# MIDIThereminCPU.net
KiCad netlist of a schematic drawn in EAGLE
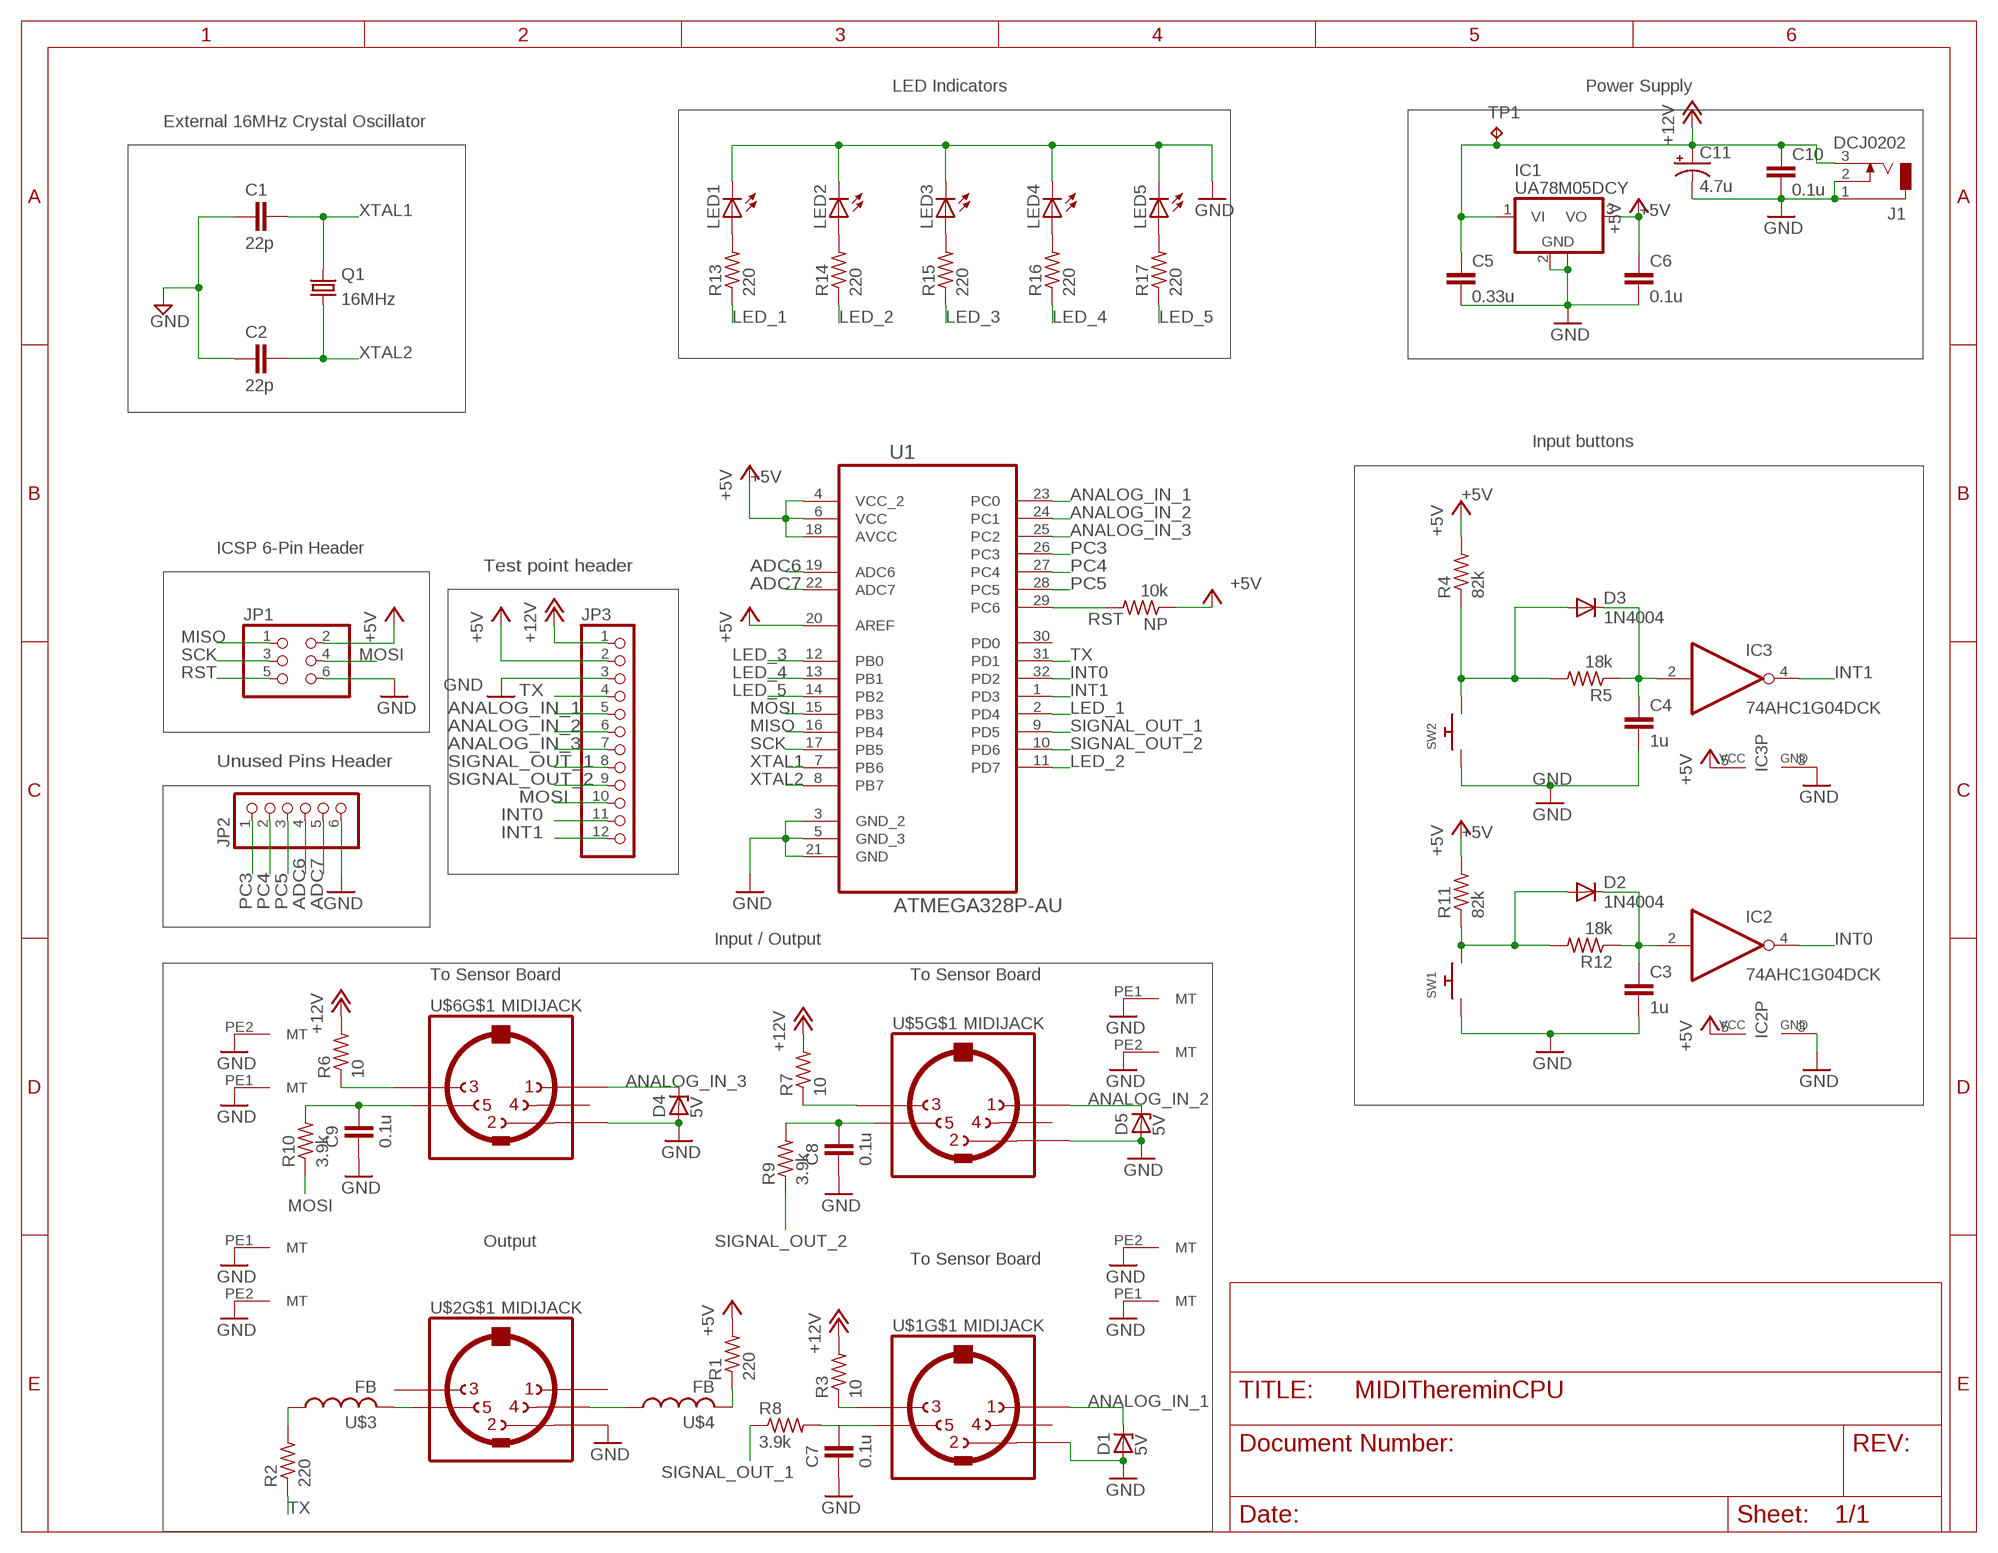
[diagram p0: schematic, sheet 1]

(export (version "E")
  (design (tool "Eeschema 10.0.6"))
  (components
    (comp (ref "C1")
      (value "22p")
      (footprint "eagle-import:C2.5-3")
      (libsource (lib "eagle-import") (part "C2,5-3"))
    )
    (comp (ref "C2")
      (value "22p")
      (footprint "eagle-import:C2.5-3")
      (libsource (lib "eagle-import") (part "C2,5-3"))
    )
    (comp (ref "C3")
      (value "1u")
      (footprint "eagle-import:C2.5-3")
      (libsource (lib "eagle-import") (part "C2,5-3"))
    )
    (comp (ref "C4")
      (value "1u")
      (footprint "eagle-import:C2.5-3")
      (libsource (lib "eagle-import") (part "C2,5-3"))
    )
    (comp (ref "C5")
      (value "0.33u")
      (footprint "eagle-import:C2.5-3")
      (libsource (lib "eagle-import") (part "C2,5-3"))
    )
    (comp (ref "C6")
      (value "0.1u")
      (footprint "eagle-import:C2.5-3")
      (libsource (lib "eagle-import") (part "C2,5-3"))
    )
    (comp (ref "C7")
      (value "0.1u")
      (footprint "eagle-import:C2.5-3")
      (libsource (lib "eagle-import") (part "C2,5-3"))
    )
    (comp (ref "C8")
      (value "0.1u")
      (footprint "eagle-import:C2.5-3")
      (libsource (lib "eagle-import") (part "C2,5-3"))
    )
    (comp (ref "C9")
      (value "0.1u")
      (footprint "eagle-import:C2.5-3")
      (libsource (lib "eagle-import") (part "C2,5-3"))
    )
    (comp (ref "C10")
      (value "0.1u")
      (footprint "eagle-import:C2.5-3")
      (libsource (lib "eagle-import") (part "C2,5-3"))
    )
    (comp (ref "C11")
      (value "4.7u")
      (footprint "eagle-import:E3,5-8")
      (libsource (lib "eagle-import") (part "CPOL-USE3.5-8"))
    )
    (comp (ref "D1")
      (value "5V")
      (footprint "eagle-import:P1Z12")
      (libsource (lib "eagle-import") (part "ZENER-DIODEP1-Z12"))
    )
    (comp (ref "D2")
      (value "1N4004")
      (footprint "eagle-import:DO41-10")
      (libsource (lib "eagle-import") (part "1N4004"))
    )
    (comp (ref "D3")
      (value "1N4004")
      (footprint "eagle-import:DO41-10")
      (libsource (lib "eagle-import") (part "1N4004"))
    )
    (comp (ref "D4")
      (value "5V")
      (footprint "eagle-import:P1Z12")
      (libsource (lib "eagle-import") (part "ZENER-DIODEP1-Z12"))
    )
    (comp (ref "D5")
      (value "5V")
      (footprint "eagle-import:P1Z12")
      (libsource (lib "eagle-import") (part "ZENER-DIODEP1-Z12"))
    )
    (comp (ref "IC1")
      (value "UA78M05DCY")
      (footprint "eagle-import:SOT223")
      (libsource (lib "eagle-import") (part "UA78MDCY05"))
    )
    (comp (ref "IC2")
      (value "74AHC1G04DCK")
      (footprint "eagle-import:SC70-5")
      (libsource (lib "eagle-import") (part "741G04DCKAHC"))
    )
    (comp (ref "IC3")
      (value "74AHC1G04DCK")
      (footprint "eagle-import:SC70-5")
      (libsource (lib "eagle-import") (part "741G04DCKAHC"))
    )
    (comp (ref "J1")
      (value "DCJ0202")
      (footprint "eagle-import:DCJ0202")
      (libsource (lib "eagle-import") (part "DCJ0202"))
    )
    (comp (ref "JP1")
      (value "PINHD-2X3")
      (footprint "eagle-import:2X03")
      (libsource (lib "eagle-import") (part "PINHD-2X3"))
    )
    (comp (ref "JP2")
      (value "PINHD-1X6")
      (footprint "eagle-import:1X06")
      (libsource (lib "eagle-import") (part "PINHD-1X6"))
    )
    (comp (ref "JP3")
      (value "PINHD-1X12")
      (footprint "eagle-import:1X12")
      (libsource (lib "eagle-import") (part "PINHD-1X12"))
    )
    (comp (ref "LED1")
      (value "LEDB155")
      (footprint "eagle-import:Q62902-B155")
      (libsource (lib "eagle-import") (part "LEDB155"))
    )
    (comp (ref "LED2")
      (value "LEDB155")
      (footprint "eagle-import:Q62902-B155")
      (libsource (lib "eagle-import") (part "LEDB155"))
    )
    (comp (ref "LED3")
      (value "LEDB155")
      (footprint "eagle-import:Q62902-B155")
      (libsource (lib "eagle-import") (part "LEDB155"))
    )
    (comp (ref "LED4")
      (value "LEDB155")
      (footprint "eagle-import:Q62902-B155")
      (libsource (lib "eagle-import") (part "LEDB155"))
    )
    (comp (ref "LED5")
      (value "LEDB155")
      (footprint "eagle-import:Q62902-B155")
      (libsource (lib "eagle-import") (part "LEDB155"))
    )
    (comp (ref "NP")
      (value "10k")
      (footprint "eagle-import:0207_10")
      (libsource (lib "eagle-import") (part "R-US_0207/10"))
    )
    (comp (ref "Q1")
      (value "16MHz")
      (footprint "eagle-import:SM49")
      (libsource (lib "eagle-import") (part "CRYSTALSM49"))
    )
    (comp (ref "R1")
      (value "220")
      (footprint "eagle-import:0207_10")
      (libsource (lib "eagle-import") (part "R-US_0207/10"))
    )
    (comp (ref "R2")
      (value "220")
      (footprint "eagle-import:0207_10")
      (libsource (lib "eagle-import") (part "R-US_0207/10"))
    )
    (comp (ref "R3")
      (value "10")
      (footprint "eagle-import:0207_10")
      (libsource (lib "eagle-import") (part "R-US_0207/10"))
    )
    (comp (ref "R4")
      (value "82k")
      (footprint "eagle-import:0207_10")
      (libsource (lib "eagle-import") (part "R-US_0207/10"))
    )
    (comp (ref "R5")
      (value "18k")
      (footprint "eagle-import:0207_10")
      (libsource (lib "eagle-import") (part "R-US_0207/10"))
    )
    (comp (ref "R6")
      (value "10")
      (footprint "eagle-import:0207_10")
      (libsource (lib "eagle-import") (part "R-US_0207/10"))
    )
    (comp (ref "R7")
      (value "10")
      (footprint "eagle-import:0207_10")
      (libsource (lib "eagle-import") (part "R-US_0207/10"))
    )
    (comp (ref "R8")
      (value "3.9k")
      (footprint "eagle-import:0207_10")
      (libsource (lib "eagle-import") (part "R-US_0207/10"))
    )
    (comp (ref "R9")
      (value "3.9k")
      (footprint "eagle-import:0207_10")
      (libsource (lib "eagle-import") (part "R-US_0207/10"))
    )
    (comp (ref "R10")
      (value "3.9k")
      (footprint "eagle-import:0207_10")
      (libsource (lib "eagle-import") (part "R-US_0207/10"))
    )
    (comp (ref "R11")
      (value "82k")
      (footprint "eagle-import:0207_10")
      (libsource (lib "eagle-import") (part "R-US_0207/10"))
    )
    (comp (ref "R12")
      (value "18k")
      (footprint "eagle-import:0207_10")
      (libsource (lib "eagle-import") (part "R-US_0207/10"))
    )
    (comp (ref "R13")
      (value "220")
      (footprint "eagle-import:0207_10")
      (libsource (lib "eagle-import") (part "R-US_0207/10"))
    )
    (comp (ref "R14")
      (value "220")
      (footprint "eagle-import:0207_10")
      (libsource (lib "eagle-import") (part "R-US_0207/10"))
    )
    (comp (ref "R15")
      (value "220")
      (footprint "eagle-import:0207_10")
      (libsource (lib "eagle-import") (part "R-US_0207/10"))
    )
    (comp (ref "R16")
      (value "220")
      (footprint "eagle-import:0207_10")
      (libsource (lib "eagle-import") (part "R-US_0207/10"))
    )
    (comp (ref "R17")
      (value "220")
      (footprint "eagle-import:0207_10")
      (libsource (lib "eagle-import") (part "R-US_0207/10"))
    )
    (comp (ref "SW1")
      (value "SWITCH_PUSHBUTTONSOFTTOUCHSMD_SJ")
      (footprint "eagle-import:PUSHBUTTON_SMD_SJ")
      (libsource (lib "eagle-import") (part "SWITCH_PUSHBUTTONSOFTTOUCHSMD_SJ"))
    )
    (comp (ref "SW2")
      (value "SWITCH_PUSHBUTTONSOFTTOUCHSMD_SJ")
      (footprint "eagle-import:PUSHBUTTON_SMD_SJ")
      (libsource (lib "eagle-import") (part "SWITCH_PUSHBUTTONSOFTTOUCHSMD_SJ"))
    )
    (comp (ref "TP1")
      (value "TPTP15SQ")
      (footprint "eagle-import:TP15SQ")
      (libsource (lib "eagle-import") (part "TPTP15SQ"))
    )
    (comp (ref "U$1")
      (value "MIDIJACK")
      (footprint "eagle-import:CP-2350")
      (libsource (lib "eagle-import") (part "MIDIJACK"))
    )
    (comp (ref "U$2")
      (value "MIDIJACK")
      (footprint "eagle-import:CP-2350")
      (libsource (lib "eagle-import") (part "MIDIJACK"))
    )
    (comp (ref "U$3") (value "FB") (footprint "eagle-import:FB") (libsource (lib "eagle-import") (part "FB")))
    (comp (ref "U$4") (value "FB") (footprint "eagle-import:FB") (libsource (lib "eagle-import") (part "FB")))
    (comp (ref "U$5")
      (value "MIDIJACK")
      (footprint "eagle-import:CP-2350")
      (libsource (lib "eagle-import") (part "MIDIJACK"))
    )
    (comp (ref "U$6")
      (value "MIDIJACK")
      (footprint "eagle-import:CP-2350")
      (libsource (lib "eagle-import") (part "MIDIJACK"))
    )
    (comp (ref "U1")
      (value "ATMEGA328P-AU")
      (footprint "eagle-import:QFP80P900X900X120-32N")
      (libsource (lib "eagle-import") (part "ATMEGA328P-AU"))
    )
  )
  (nets
    (net (code "1") (name "+5V") (class "Default")
      (node (ref "C6") (pin "1") (pinfunction "1_1") (pintype "passive"))
      (node (ref "IC1") (pin "3") (pinfunction "VO_3") (pintype "passive"))
      (node (ref "IC2") (pin "5") (pinfunction "VCC_5") (pintype "power_in"))
      (node (ref "IC3") (pin "5") (pinfunction "VCC_5") (pintype "power_in"))
      (node (ref "JP1") (pin "2") (pinfunction "2_2") (pintype "passive"))
      (node (ref "JP3") (pin "2") (pinfunction "2_2") (pintype "passive"))
      (node (ref "NP") (pin "1") (pinfunction "1_1") (pintype "passive"))
      (node (ref "R1") (pin "2") (pinfunction "2_2") (pintype "passive"))
      (node (ref "R11") (pin "2") (pinfunction "2_2") (pintype "passive"))
      (node (ref "R4") (pin "2") (pinfunction "2_2") (pintype "passive"))
      (node (ref "U1") (pin "18") (pinfunction "AVCC_18") (pintype "power_in"))
      (node (ref "U1") (pin "20") (pinfunction "AREF_20") (pintype "input"))
      (node (ref "U1") (pin "4") (pinfunction "VCC_2_4") (pintype "power_in"))
      (node (ref "U1") (pin "6") (pinfunction "VCC_6") (pintype "power_in"))
    )
    (net (code "2") (name "+12V") (class "Default")
      (node (ref "C10") (pin "1") (pinfunction "1_1") (pintype "passive"))
      (node (ref "C11") (pin "+") (pinfunction "+_+") (pintype "passive"))
      (node (ref "C5") (pin "1") (pinfunction "1_1") (pintype "passive"))
      (node (ref "IC1") (pin "1") (pinfunction "VI_1") (pintype "input"))
      (node (ref "J1") (pin "3") (pinfunction "3_3") (pintype "passive"))
      (node (ref "JP3") (pin "1") (pinfunction "1_1") (pintype "passive"))
      (node (ref "R3") (pin "2") (pinfunction "2_2") (pintype "passive"))
      (node (ref "R6") (pin "2") (pinfunction "2_2") (pintype "passive"))
      (node (ref "R7") (pin "2") (pinfunction "2_2") (pintype "passive"))
      (node (ref "TP1") (pin "TP") (pinfunction "TP_TP") (pintype "input"))
    )
    (net (code "3") (name "/ADC6") (class "Default")
      (node (ref "JP2") (pin "4") (pinfunction "4_4") (pintype "passive"))
      (node (ref "U1") (pin "19") (pinfunction "ADC6_19") (pintype "input"))
    )
    (net (code "4") (name "/ADC7") (class "Default")
      (node (ref "JP2") (pin "5") (pinfunction "5_5") (pintype "passive"))
      (node (ref "U1") (pin "22") (pinfunction "ADC7_22") (pintype "input"))
    )
    (net (code "5") (name "/ANALOG_IN_1") (class "Default")
      (node (ref "D1") (pin "C") (pinfunction "C_C") (pintype "passive"))
      (node (ref "JP3") (pin "5") (pinfunction "5_5") (pintype "passive"))
      (node (ref "U$1") (pin "1") (pinfunction "1_1") (pintype "passive"))
      (node (ref "U1") (pin "23") (pinfunction "PC0_23") (pintype "bidirectional"))
    )
    (net (code "6") (name "/ANALOG_IN_2") (class "Default")
      (node (ref "D5") (pin "C") (pinfunction "C_C") (pintype "passive"))
      (node (ref "JP3") (pin "6") (pinfunction "6_6") (pintype "passive"))
      (node (ref "U$5") (pin "1") (pinfunction "1_1") (pintype "passive"))
      (node (ref "U1") (pin "24") (pinfunction "PC1_24") (pintype "bidirectional"))
    )
    (net (code "7") (name "/ANALOG_IN_3") (class "Default")
      (node (ref "D4") (pin "C") (pinfunction "C_C") (pintype "passive"))
      (node (ref "JP3") (pin "7") (pinfunction "7_7") (pintype "passive"))
      (node (ref "U$6") (pin "1") (pinfunction "1_1") (pintype "passive"))
      (node (ref "U1") (pin "25") (pinfunction "PC2_25") (pintype "bidirectional"))
    )
    (net (code "8") (name "/INT0") (class "Default")
      (node (ref "IC2") (pin "4") (pinfunction "O_4") (pintype "output"))
      (node (ref "JP3") (pin "11") (pinfunction "11_11") (pintype "passive"))
      (node (ref "U1") (pin "32") (pinfunction "PD2_32") (pintype "bidirectional"))
    )
    (net (code "9") (name "/INT1") (class "Default")
      (node (ref "IC3") (pin "4") (pinfunction "O_4") (pintype "output"))
      (node (ref "JP3") (pin "12") (pinfunction "12_12") (pintype "passive"))
      (node (ref "U1") (pin "1") (pinfunction "PD3_1") (pintype "bidirectional"))
    )
    (net (code "10") (name "/LED_1") (class "Default")
      (node (ref "R13") (pin "1") (pinfunction "1_1") (pintype "passive"))
      (node (ref "U1") (pin "2") (pinfunction "PD4_2") (pintype "bidirectional"))
    )
    (net (code "11") (name "/LED_2") (class "Default")
      (node (ref "R14") (pin "1") (pinfunction "1_1") (pintype "passive"))
      (node (ref "U1") (pin "11") (pinfunction "PD7_11") (pintype "bidirectional"))
    )
    (net (code "12") (name "/LED_3") (class "Default")
      (node (ref "R15") (pin "1") (pinfunction "1_1") (pintype "passive"))
      (node (ref "U1") (pin "12") (pinfunction "PB0_12") (pintype "bidirectional"))
    )
    (net (code "13") (name "/LED_4") (class "Default")
      (node (ref "R16") (pin "1") (pinfunction "1_1") (pintype "passive"))
      (node (ref "U1") (pin "13") (pinfunction "PB1_13") (pintype "bidirectional"))
    )
    (net (code "14") (name "/LED_5") (class "Default")
      (node (ref "R17") (pin "1") (pinfunction "1_1") (pintype "passive"))
      (node (ref "U1") (pin "14") (pinfunction "PB2_14") (pintype "bidirectional"))
    )
    (net (code "15") (name "/MISO") (class "Default")
      (node (ref "JP1") (pin "1") (pinfunction "1_1") (pintype "passive"))
      (node (ref "U1") (pin "16") (pinfunction "PB4_16") (pintype "bidirectional"))
    )
    (net (code "16") (name "/MOSI") (class "Default")
      (node (ref "JP1") (pin "4") (pinfunction "4_4") (pintype "passive"))
      (node (ref "JP3") (pin "10") (pinfunction "10_10") (pintype "passive"))
      (node (ref "R10") (pin "1") (pinfunction "1_1") (pintype "passive"))
      (node (ref "U1") (pin "15") (pinfunction "PB3_15") (pintype "bidirectional"))
    )
    (net (code "17") (name "/PC3") (class "Default")
      (node (ref "JP2") (pin "1") (pinfunction "1_1") (pintype "passive"))
      (node (ref "U1") (pin "26") (pinfunction "PC3_26") (pintype "bidirectional"))
    )
    (net (code "18") (name "/PC4") (class "Default")
      (node (ref "JP2") (pin "2") (pinfunction "2_2") (pintype "passive"))
      (node (ref "U1") (pin "27") (pinfunction "PC4_27") (pintype "bidirectional"))
    )
    (net (code "19") (name "/PC5") (class "Default")
      (node (ref "JP2") (pin "3") (pinfunction "3_3") (pintype "passive"))
      (node (ref "U1") (pin "28") (pinfunction "PC5_28") (pintype "bidirectional"))
    )
    (net (code "20") (name "/RST") (class "Default")
      (node (ref "JP1") (pin "5") (pinfunction "5_5") (pintype "passive"))
      (node (ref "NP") (pin "2") (pinfunction "2_2") (pintype "passive"))
      (node (ref "U1") (pin "29") (pinfunction "PC6_29") (pintype "bidirectional"))
    )
    (net (code "21") (name "/SCK") (class "Default")
      (node (ref "JP1") (pin "3") (pinfunction "3_3") (pintype "passive"))
      (node (ref "U1") (pin "17") (pinfunction "PB5_17") (pintype "bidirectional"))
    )
    (net (code "22") (name "/SIGNAL_OUT_1") (class "Default")
      (node (ref "JP3") (pin "8") (pinfunction "8_8") (pintype "passive"))
      (node (ref "R8") (pin "1") (pinfunction "1_1") (pintype "passive"))
      (node (ref "U1") (pin "9") (pinfunction "PD5_9") (pintype "bidirectional"))
    )
    (net (code "23") (name "/SIGNAL_OUT_2") (class "Default")
      (node (ref "JP3") (pin "9") (pinfunction "9_9") (pintype "passive"))
      (node (ref "R9") (pin "1") (pinfunction "1_1") (pintype "passive"))
      (node (ref "U1") (pin "10") (pinfunction "PD6_10") (pintype "bidirectional"))
    )
    (net (code "24") (name "/TX") (class "Default")
      (node (ref "JP3") (pin "4") (pinfunction "4_4") (pintype "passive"))
      (node (ref "R2") (pin "1") (pinfunction "1_1") (pintype "passive"))
      (node (ref "U1") (pin "31") (pinfunction "PD1_31") (pintype "bidirectional"))
    )
    (net (code "25") (name "/XTAL1") (class "Default")
      (node (ref "C1") (pin "2") (pinfunction "2_2") (pintype "passive"))
      (node (ref "Q1") (pin "2") (pinfunction "2_2") (pintype "passive"))
      (node (ref "U1") (pin "7") (pinfunction "PB6_7") (pintype "bidirectional"))
    )
    (net (code "26") (name "/XTAL2") (class "Default")
      (node (ref "C2") (pin "2") (pinfunction "2_2") (pintype "passive"))
      (node (ref "Q1") (pin "1") (pinfunction "1_1") (pintype "passive"))
      (node (ref "U1") (pin "8") (pinfunction "PB7_8") (pintype "bidirectional"))
    )
    (net (code "27") (name "GND") (class "Default")
      (node (ref "C1") (pin "1") (pinfunction "1_1") (pintype "passive"))
      (node (ref "C10") (pin "2") (pinfunction "2_2") (pintype "passive"))
      (node (ref "C11") (pin "-") (pinfunction "-_-") (pintype "passive"))
      (node (ref "C2") (pin "1") (pinfunction "1_1") (pintype "passive"))
      (node (ref "C3") (pin "2") (pinfunction "2_2") (pintype "passive"))
      (node (ref "C4") (pin "2") (pinfunction "2_2") (pintype "passive"))
      (node (ref "C5") (pin "2") (pinfunction "2_2") (pintype "passive"))
      (node (ref "C6") (pin "2") (pinfunction "2_2") (pintype "passive"))
      (node (ref "C7") (pin "1") (pinfunction "1_1") (pintype "passive"))
      (node (ref "C8") (pin "1") (pinfunction "1_1") (pintype "passive"))
      (node (ref "C9") (pin "1") (pinfunction "1_1") (pintype "passive"))
      (node (ref "D1") (pin "A") (pinfunction "A_A") (pintype "passive"))
      (node (ref "D4") (pin "A") (pinfunction "A_A") (pintype "passive"))
      (node (ref "D5") (pin "A") (pinfunction "A_A") (pintype "passive"))
      (node (ref "IC1") (pin "2") (pinfunction "GND_2") (pintype "passive"))
      (node (ref "IC1") (pin "4") (pinfunction "GND_4") (pintype "passive"))
      (node (ref "IC2") (pin "3") (pinfunction "GND_3") (pintype "power_in"))
      (node (ref "IC3") (pin "3") (pinfunction "GND_3") (pintype "power_in"))
      (node (ref "J1") (pin "1") (pinfunction "1_1") (pintype "passive"))
      (node (ref "J1") (pin "2") (pinfunction "2_2") (pintype "passive"))
      (node (ref "JP1") (pin "6") (pinfunction "6_6") (pintype "passive"))
      (node (ref "JP2") (pin "6") (pinfunction "6_6") (pintype "passive"))
      (node (ref "JP3") (pin "3") (pinfunction "3_3") (pintype "passive"))
      (node (ref "LED1") (pin "K") (pinfunction "C_K") (pintype "passive"))
      (node (ref "LED2") (pin "K") (pinfunction "C_K") (pintype "passive"))
      (node (ref "LED3") (pin "K") (pinfunction "C_K") (pintype "passive"))
      (node (ref "LED4") (pin "K") (pinfunction "C_K") (pintype "passive"))
      (node (ref "LED5") (pin "K") (pinfunction "C_K") (pintype "passive"))
      (node (ref "SW1") (pin "P$1") (pinfunction "P$1_P$1") (pintype "passive"))
      (node (ref "SW2") (pin "P$1") (pinfunction "P$1_P$1") (pintype "passive"))
      (node (ref "U$1") (pin "2") (pinfunction "2_2") (pintype "passive"))
      (node (ref "U$1") (pin "PE1") (pinfunction "MT_PE1") (pintype "passive"))
      (node (ref "U$1") (pin "PE2") (pinfunction "MT_PE2") (pintype "passive"))
      (node (ref "U$2") (pin "2") (pinfunction "2_2") (pintype "passive"))
      (node (ref "U$2") (pin "PE1") (pinfunction "MT_PE1") (pintype "passive"))
      (node (ref "U$2") (pin "PE2") (pinfunction "MT_PE2") (pintype "passive"))
      (node (ref "U$5") (pin "2") (pinfunction "2_2") (pintype "passive"))
      (node (ref "U$5") (pin "PE1") (pinfunction "MT_PE1") (pintype "passive"))
      (node (ref "U$5") (pin "PE2") (pinfunction "MT_PE2") (pintype "passive"))
      (node (ref "U$6") (pin "2") (pinfunction "2_2") (pintype "passive"))
      (node (ref "U$6") (pin "PE1") (pinfunction "MT_PE1") (pintype "passive"))
      (node (ref "U$6") (pin "PE2") (pinfunction "MT_PE2") (pintype "passive"))
      (node (ref "U1") (pin "21") (pinfunction "GND_21") (pintype "passive"))
      (node (ref "U1") (pin "3") (pinfunction "GND_2_3") (pintype "passive"))
      (node (ref "U1") (pin "5") (pinfunction "GND_3_5") (pintype "passive"))
    )
    (net (code "28") (name "Net-(C7-Pad2)") (class "Default")
      (node (ref "C7") (pin "2") (pinfunction "2_2") (pintype "passive"))
      (node (ref "R8") (pin "2") (pinfunction "2_2") (pintype "passive"))
      (node (ref "U$1") (pin "5") (pinfunction "5_5") (pintype "passive"))
    )
    (net (code "29") (name "Net-(C8-Pad2)") (class "Default")
      (node (ref "C8") (pin "2") (pinfunction "2_2") (pintype "passive"))
      (node (ref "R9") (pin "2") (pinfunction "2_2") (pintype "passive"))
      (node (ref "U$5") (pin "5") (pinfunction "5_5") (pintype "passive"))
    )
    (net (code "30") (name "Net-(C9-Pad2)") (class "Default")
      (node (ref "C9") (pin "2") (pinfunction "2_2") (pintype "passive"))
      (node (ref "R10") (pin "2") (pinfunction "2_2") (pintype "passive"))
      (node (ref "U$6") (pin "5") (pinfunction "5_5") (pintype "passive"))
    )
    (net (code "31") (name "Net-(D2-PadA)") (class "Default")
      (node (ref "D2") (pin "A") (pinfunction "A_A") (pintype "passive"))
      (node (ref "R11") (pin "1") (pinfunction "1_1") (pintype "passive"))
      (node (ref "R12") (pin "2") (pinfunction "2_2") (pintype "passive"))
      (node (ref "SW1") (pin "P$2") (pinfunction "P$2_P$2") (pintype "passive"))
    )
    (net (code "32") (name "Net-(D3-PadA)") (class "Default")
      (node (ref "D3") (pin "A") (pinfunction "A_A") (pintype "passive"))
      (node (ref "R4") (pin "1") (pinfunction "1_1") (pintype "passive"))
      (node (ref "R5") (pin "2") (pinfunction "2_2") (pintype "passive"))
      (node (ref "SW2") (pin "P$2") (pinfunction "P$2_P$2") (pintype "passive"))
    )
    (net (code "33") (name "Net-(IC2A-I)") (class "Default")
      (node (ref "C3") (pin "1") (pinfunction "1_1") (pintype "passive"))
      (node (ref "D2") (pin "C") (pinfunction "C_C") (pintype "passive"))
      (node (ref "IC2") (pin "2") (pinfunction "I_2") (pintype "input"))
      (node (ref "R12") (pin "1") (pinfunction "1_1") (pintype "passive"))
    )
    (net (code "34") (name "Net-(IC3A-I)") (class "Default")
      (node (ref "C4") (pin "1") (pinfunction "1_1") (pintype "passive"))
      (node (ref "D3") (pin "C") (pinfunction "C_C") (pintype "passive"))
      (node (ref "IC3") (pin "2") (pinfunction "I_2") (pintype "input"))
      (node (ref "R5") (pin "1") (pinfunction "1_1") (pintype "passive"))
    )
    (net (code "35") (name "Net-(LED1-PadA)") (class "Default")
      (node (ref "LED1") (pin "A") (pinfunction "A_A") (pintype "passive"))
      (node (ref "R13") (pin "2") (pinfunction "2_2") (pintype "passive"))
    )
    (net (code "36") (name "Net-(LED2-PadA)") (class "Default")
      (node (ref "LED2") (pin "A") (pinfunction "A_A") (pintype "passive"))
      (node (ref "R14") (pin "2") (pinfunction "2_2") (pintype "passive"))
    )
    (net (code "37") (name "Net-(LED3-PadA)") (class "Default")
      (node (ref "LED3") (pin "A") (pinfunction "A_A") (pintype "passive"))
      (node (ref "R15") (pin "2") (pinfunction "2_2") (pintype "passive"))
    )
    (net (code "38") (name "Net-(LED4-PadA)") (class "Default")
      (node (ref "LED4") (pin "A") (pinfunction "A_A") (pintype "passive"))
      (node (ref "R16") (pin "2") (pinfunction "2_2") (pintype "passive"))
    )
    (net (code "39") (name "Net-(LED5-PadA)") (class "Default")
      (node (ref "LED5") (pin "A") (pinfunction "A_A") (pintype "passive"))
      (node (ref "R17") (pin "2") (pinfunction "2_2") (pintype "passive"))
    )
    (net (code "40") (name "Net-(R3-Pad1)") (class "Default")
      (node (ref "R3") (pin "1") (pinfunction "1_1") (pintype "passive"))
      (node (ref "U$1") (pin "3") (pinfunction "3_3") (pintype "passive"))
    )
    (net (code "41") (name "Net-(R6-Pad1)") (class "Default")
      (node (ref "R6") (pin "1") (pinfunction "1_1") (pintype "passive"))
      (node (ref "U$6") (pin "3") (pinfunction "3_3") (pintype "passive"))
    )
    (net (code "42") (name "Net-(R7-Pad1)") (class "Default")
      (node (ref "R7") (pin "1") (pinfunction "1_1") (pintype "passive"))
      (node (ref "U$5") (pin "3") (pinfunction "3_3") (pintype "passive"))
    )
    (net (code "43") (name "Net-(U$3-1)") (class "Default")
      (node (ref "R2") (pin "2") (pinfunction "2_2") (pintype "passive"))
      (node (ref "U$3") (pin "P$1") (pinfunction "1_P$1") (pintype "passive"))
    )
    (net (code "44") (name "Net-(U$3-2)") (class "Default")
      (node (ref "U$2") (pin "5") (pinfunction "5_5") (pintype "passive"))
      (node (ref "U$3") (pin "P$2") (pinfunction "2_P$2") (pintype "passive"))
    )
    (net (code "45") (name "Net-(U$4-1)") (class "Default")
      (node (ref "U$2") (pin "4") (pinfunction "4_4") (pintype "passive"))
      (node (ref "U$4") (pin "P$1") (pinfunction "1_P$1") (pintype "passive"))
    )
    (net (code "46") (name "Net-(U$4-2)") (class "Default")
      (node (ref "R1") (pin "1") (pinfunction "1_1") (pintype "passive"))
      (node (ref "U$4") (pin "P$2") (pinfunction "2_P$2") (pintype "passive"))
    )
    (net (code "47") (name "unconnected-(U$1-Pad4)") (class "Default")
      (node (ref "U$1") (pin "4") (pinfunction "4_4") (pintype "passive"))
    )
    (net (code "48") (name "unconnected-(U$2-Pad1)") (class "Default")
      (node (ref "U$2") (pin "1") (pinfunction "1_1") (pintype "passive"))
    )
    (net (code "49") (name "unconnected-(U$2-Pad3)") (class "Default")
      (node (ref "U$2") (pin "3") (pinfunction "3_3") (pintype "passive"))
    )
    (net (code "50") (name "unconnected-(U$5-Pad4)") (class "Default")
      (node (ref "U$5") (pin "4") (pinfunction "4_4") (pintype "passive"))
    )
    (net (code "51") (name "unconnected-(U$6-Pad4)") (class "Default")
      (node (ref "U$6") (pin "4") (pinfunction "4_4") (pintype "passive"))
    )
    (net (code "52") (name "unconnected-(U1-PD0-Pad30)") (class "Default")
      (node (ref "U1") (pin "30") (pinfunction "PD0_30") (pintype "bidirectional"))
    )
  )
)
